# T07_-Schematic_V3.net
KiCad netlist of a schematic drawn in EAGLE
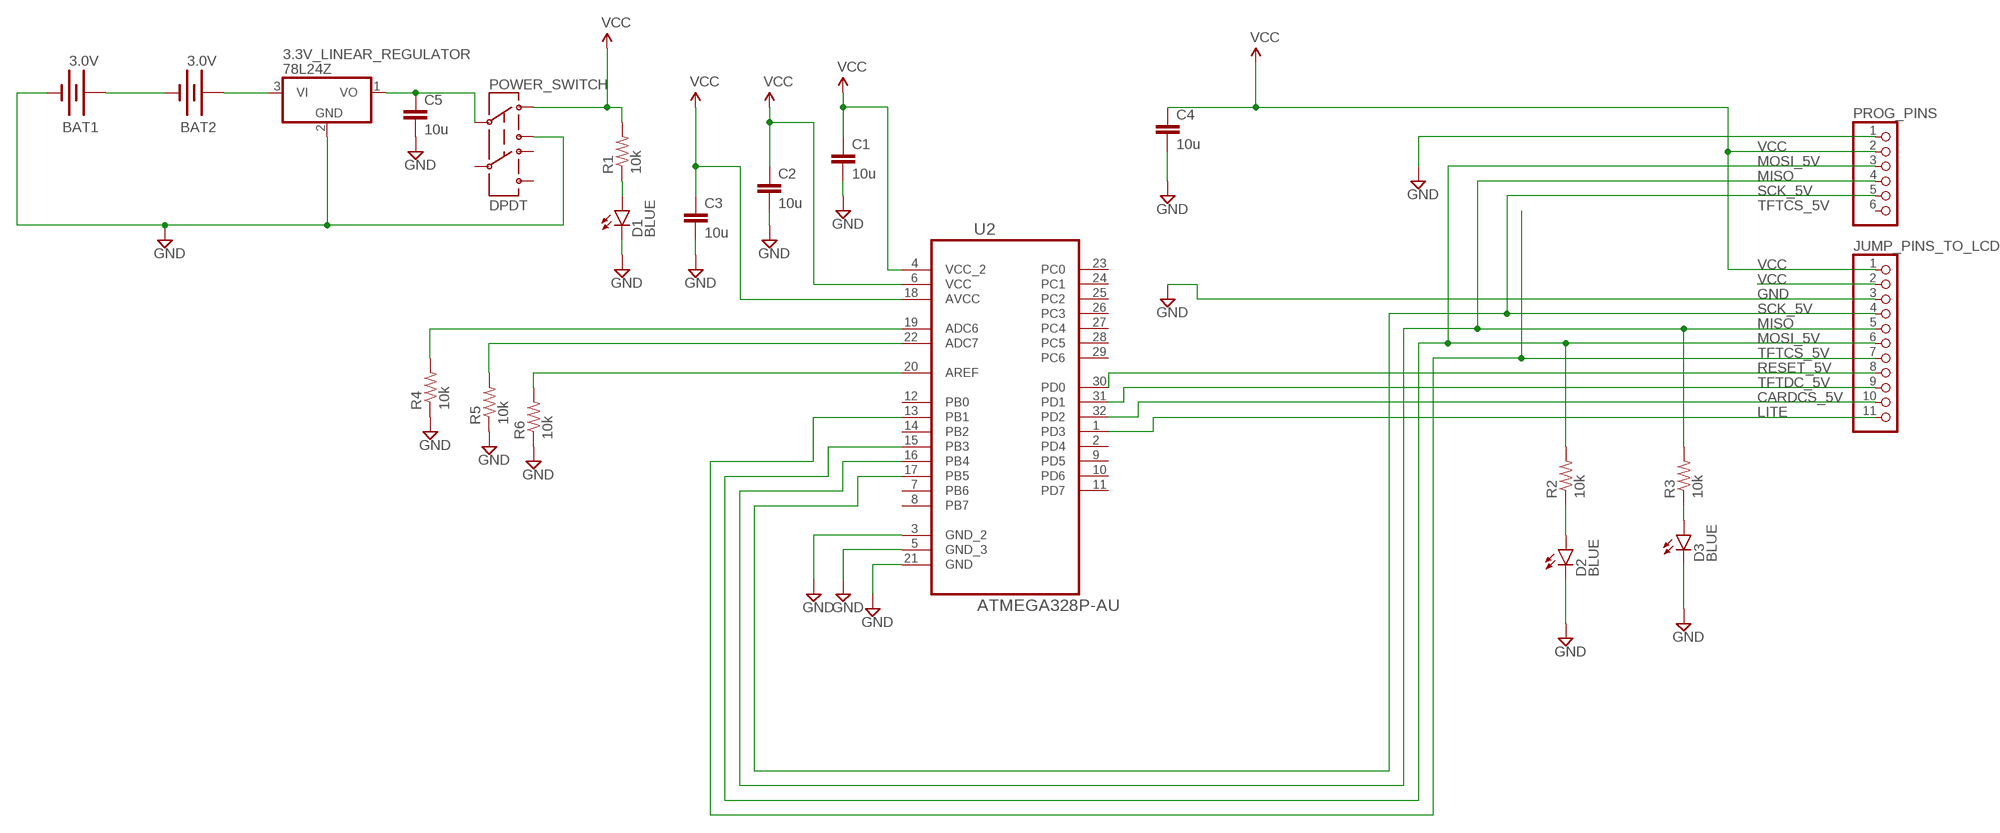
[diagram p0: schematic, sheet 1]

(export (version "E")
  (design (tool "Eeschema 10.0.6"))
  (components
    (comp (ref "3.3V_LINEAR_REGULATOR")
      (value "78L24Z")
      (footprint "eagle-import:TO92")
      (libsource (lib "eagle-import") (part "78ZL24"))
    )
    (comp (ref "BAT1")
      (value "3.0V")
      (footprint "eagle-import:BATTCON_245MM_PTH")
      (libsource (lib "eagle-import") (part "BATTERY245PTH"))
    )
    (comp (ref "BAT2")
      (value "3.0V")
      (footprint "eagle-import:BATTCON_245MM_PTH")
      (libsource (lib "eagle-import") (part "BATTERY245PTH"))
    )
    (comp (ref "C1")
      (value "10u")
      (footprint "eagle-import:1206")
      (libsource (lib "eagle-import") (part "CAP1206"))
    )
    (comp (ref "C2")
      (value "10u")
      (footprint "eagle-import:1206")
      (libsource (lib "eagle-import") (part "CAP1206"))
    )
    (comp (ref "C3")
      (value "10u")
      (footprint "eagle-import:1206")
      (libsource (lib "eagle-import") (part "CAP1206"))
    )
    (comp (ref "C4")
      (value "10u")
      (footprint "eagle-import:1206")
      (libsource (lib "eagle-import") (part "CAP1206"))
    )
    (comp (ref "C5")
      (value "10u")
      (footprint "eagle-import:1206")
      (libsource (lib "eagle-import") (part "CAP1206"))
    )
    (comp (ref "D1")
      (value "BLUE")
      (footprint "eagle-import:LED-1206")
      (libsource (lib "eagle-import") (part "LED-BLUE1206"))
    )
    (comp (ref "D2")
      (value "BLUE")
      (footprint "eagle-import:LED-1206")
      (libsource (lib "eagle-import") (part "LED-BLUE1206"))
    )
    (comp (ref "D3")
      (value "BLUE")
      (footprint "eagle-import:LED-1206")
      (libsource (lib "eagle-import") (part "LED-BLUE1206"))
    )
    (comp (ref "JUMP_PINS_TO_LCD")
      (value "HEADER-1X1176MIL")
      (footprint "eagle-import:1X11_ROUND_76")
      (libsource (lib "eagle-import") (part "HEADER-1X1176MIL"))
    )
    (comp (ref "POWER_SWITCH")
      (value "DPDT")
      (footprint "eagle-import:AYZ0202")
      (libsource (lib "eagle-import") (part "SWITCH-DPDTAYZ0202"))
    )
    (comp (ref "PROG_PINS")
      (value "PINHD-1X6-3.5MM")
      (footprint "eagle-import:1X06-3.5MM")
      (libsource (lib "eagle-import") (part "PINHD-1X6-3.5MM"))
    )
    (comp (ref "R1")
      (value "10k")
      (footprint "eagle-import:1206")
      (libsource (lib "eagle-import") (part "RESISTOR1206"))
    )
    (comp (ref "R2")
      (value "10k")
      (footprint "eagle-import:1206")
      (libsource (lib "eagle-import") (part "RESISTOR1206"))
    )
    (comp (ref "R3")
      (value "10k")
      (footprint "eagle-import:1206")
      (libsource (lib "eagle-import") (part "RESISTOR1206"))
    )
    (comp (ref "R4")
      (value "10k")
      (footprint "eagle-import:1206")
      (libsource (lib "eagle-import") (part "RESISTOR1206"))
    )
    (comp (ref "R5")
      (value "10k")
      (footprint "eagle-import:1206")
      (libsource (lib "eagle-import") (part "RESISTOR1206"))
    )
    (comp (ref "R6")
      (value "10k")
      (footprint "eagle-import:1206")
      (libsource (lib "eagle-import") (part "RESISTOR1206"))
    )
    (comp (ref "U2")
      (value "ATMEGA328P-AU")
      (footprint "eagle-import:QFP80P900X900X120-32N")
      (libsource (lib "eagle-import") (part "ATMEGA328P-AU"))
    )
  )
  (nets
    (net (code "1") (name "/CARDCS_5V") (class "Default")
      (node (ref "JUMP_PINS_TO_LCD") (pin "10") (pinfunction "10_10") (pintype "passive"))
      (node (ref "U2") (pin "32") (pinfunction "PD2_32") (pintype "bidirectional"))
    )
    (net (code "2") (name "/LITE") (class "Default")
      (node (ref "JUMP_PINS_TO_LCD") (pin "11") (pinfunction "11_11") (pintype "passive"))
      (node (ref "U2") (pin "1") (pinfunction "PD3_1") (pintype "bidirectional"))
    )
    (net (code "3") (name "/MISO") (class "Default")
      (node (ref "JUMP_PINS_TO_LCD") (pin "5") (pinfunction "5_5") (pintype "passive"))
      (node (ref "PROG_PINS") (pin "4") (pinfunction "4_4") (pintype "passive"))
      (node (ref "R3") (pin "2") (pinfunction "2_2") (pintype "passive"))
      (node (ref "U2") (pin "16") (pinfunction "PB4_16") (pintype "bidirectional"))
    )
    (net (code "4") (name "/MOSI_5V") (class "Default")
      (node (ref "JUMP_PINS_TO_LCD") (pin "6") (pinfunction "6_6") (pintype "passive"))
      (node (ref "PROG_PINS") (pin "3") (pinfunction "3_3") (pintype "passive"))
      (node (ref "R2") (pin "2") (pinfunction "2_2") (pintype "passive"))
      (node (ref "U2") (pin "15") (pinfunction "PB3_15") (pintype "bidirectional"))
    )
    (net (code "5") (name "/RESET_5V") (class "Default")
      (node (ref "JUMP_PINS_TO_LCD") (pin "8") (pinfunction "8_8") (pintype "passive"))
      (node (ref "U2") (pin "30") (pinfunction "PD0_30") (pintype "bidirectional"))
    )
    (net (code "6") (name "/SCK_5V") (class "Default")
      (node (ref "JUMP_PINS_TO_LCD") (pin "4") (pinfunction "4_4") (pintype "passive"))
      (node (ref "PROG_PINS") (pin "5") (pinfunction "5_5") (pintype "passive"))
      (node (ref "U2") (pin "17") (pinfunction "PB5_17") (pintype "bidirectional"))
    )
    (net (code "7") (name "/TFTCS_5V") (class "Default")
      (node (ref "JUMP_PINS_TO_LCD") (pin "7") (pinfunction "7_7") (pintype "passive"))
      (node (ref "U2") (pin "13") (pinfunction "PB1_13") (pintype "bidirectional"))
    )
    (net (code "8") (name "/TFTDC_5V") (class "Default")
      (node (ref "JUMP_PINS_TO_LCD") (pin "9") (pinfunction "9_9") (pintype "passive"))
      (node (ref "U2") (pin "31") (pinfunction "PD1_31") (pintype "bidirectional"))
    )
    (net (code "9") (name "GND") (class "Default")
      (node (ref "3.3V_LINEAR_REGULATOR") (pin "2") (pinfunction "GND_2") (pintype "passive"))
      (node (ref "BAT1") (pin "2") (pinfunction "-_2") (pintype "power_in"))
      (node (ref "C1") (pin "2") (pinfunction "2_2") (pintype "passive"))
      (node (ref "C2") (pin "2") (pinfunction "2_2") (pintype "passive"))
      (node (ref "C3") (pin "2") (pinfunction "2_2") (pintype "passive"))
      (node (ref "C4") (pin "2") (pinfunction "2_2") (pintype "passive"))
      (node (ref "C5") (pin "2") (pinfunction "2_2") (pintype "passive"))
      (node (ref "D1") (pin "C") (pinfunction "C_C") (pintype "passive"))
      (node (ref "D2") (pin "C") (pinfunction "C_C") (pintype "passive"))
      (node (ref "D3") (pin "C") (pinfunction "C_C") (pintype "passive"))
      (node (ref "JUMP_PINS_TO_LCD") (pin "3") (pinfunction "3_3") (pintype "passive"))
      (node (ref "POWER_SWITCH") (pin "3") (pinfunction "3_3") (pintype "bidirectional"))
      (node (ref "PROG_PINS") (pin "1") (pinfunction "1_1") (pintype "passive"))
      (node (ref "R4") (pin "1") (pinfunction "1_1") (pintype "passive"))
      (node (ref "R5") (pin "1") (pinfunction "1_1") (pintype "passive"))
      (node (ref "R6") (pin "1") (pinfunction "1_1") (pintype "passive"))
      (node (ref "U2") (pin "21") (pinfunction "GND_21") (pintype "passive"))
      (node (ref "U2") (pin "3") (pinfunction "GND_2_3") (pintype "passive"))
      (node (ref "U2") (pin "5") (pinfunction "GND_3_5") (pintype "passive"))
    )
    (net (code "10") (name "Net-(3.3V_LINEAR_REGULATOR-VI)") (class "Default")
      (node (ref "3.3V_LINEAR_REGULATOR") (pin "3") (pinfunction "VI_3") (pintype "input"))
      (node (ref "BAT2") (pin "3") (pinfunction "+_3") (pintype "power_in"))
    )
    (net (code "11") (name "Net-(3.3V_LINEAR_REGULATOR-VO)") (class "Default")
      (node (ref "3.3V_LINEAR_REGULATOR") (pin "1") (pinfunction "VO_1") (pintype "passive"))
      (node (ref "C5") (pin "1") (pinfunction "1_1") (pintype "passive"))
      (node (ref "POWER_SWITCH") (pin "2") (pinfunction "2_2") (pintype "bidirectional"))
    )
    (net (code "12") (name "Net-(BAT1-+)") (class "Default")
      (node (ref "BAT1") (pin "3") (pinfunction "+_3") (pintype "power_in"))
      (node (ref "BAT2") (pin "2") (pinfunction "-_2") (pintype "power_in"))
    )
    (net (code "13") (name "Net-(D1-PadA)") (class "Default")
      (node (ref "D1") (pin "A") (pinfunction "A_A") (pintype "passive"))
      (node (ref "R1") (pin "1") (pinfunction "1_1") (pintype "passive"))
    )
    (net (code "14") (name "Net-(D2-PadA)") (class "Default")
      (node (ref "D2") (pin "A") (pinfunction "A_A") (pintype "passive"))
      (node (ref "R2") (pin "1") (pinfunction "1_1") (pintype "passive"))
    )
    (net (code "15") (name "Net-(D3-PadA)") (class "Default")
      (node (ref "D3") (pin "A") (pinfunction "A_A") (pintype "passive"))
      (node (ref "R3") (pin "1") (pinfunction "1_1") (pintype "passive"))
    )
    (net (code "16") (name "Net-(U2-ADC6)") (class "Default")
      (node (ref "R4") (pin "2") (pinfunction "2_2") (pintype "passive"))
      (node (ref "U2") (pin "19") (pinfunction "ADC6_19") (pintype "input"))
    )
    (net (code "17") (name "Net-(U2-ADC7)") (class "Default")
      (node (ref "R5") (pin "2") (pinfunction "2_2") (pintype "passive"))
      (node (ref "U2") (pin "22") (pinfunction "ADC7_22") (pintype "input"))
    )
    (net (code "18") (name "Net-(U2-AREF)") (class "Default")
      (node (ref "R6") (pin "2") (pinfunction "2_2") (pintype "passive"))
      (node (ref "U2") (pin "20") (pinfunction "AREF_20") (pintype "input"))
    )
    (net (code "19") (name "VCC") (class "Default")
      (node (ref "C1") (pin "1") (pinfunction "1_1") (pintype "passive"))
      (node (ref "C2") (pin "1") (pinfunction "1_1") (pintype "passive"))
      (node (ref "C3") (pin "1") (pinfunction "1_1") (pintype "passive"))
      (node (ref "C4") (pin "1") (pinfunction "1_1") (pintype "passive"))
      (node (ref "JUMP_PINS_TO_LCD") (pin "1") (pinfunction "1_1") (pintype "passive"))
      (node (ref "POWER_SWITCH") (pin "1") (pinfunction "1_1") (pintype "bidirectional"))
      (node (ref "PROG_PINS") (pin "2") (pinfunction "2_2") (pintype "passive"))
      (node (ref "R1") (pin "2") (pinfunction "2_2") (pintype "passive"))
      (node (ref "U2") (pin "18") (pinfunction "AVCC_18") (pintype "power_in"))
      (node (ref "U2") (pin "4") (pinfunction "VCC_2_4") (pintype "power_in"))
      (node (ref "U2") (pin "6") (pinfunction "VCC_6") (pintype "power_in"))
    )
    (net (code "20") (name "unconnected-(JUMP_PINS_TO_LCD-Pad2)") (class "Default")
      (node (ref "JUMP_PINS_TO_LCD") (pin "2") (pinfunction "2_2") (pintype "passive"))
    )
    (net (code "21") (name "unconnected-(POWER_SWITCH-Pad4)") (class "Default")
      (node (ref "POWER_SWITCH") (pin "4") (pinfunction "4_4") (pintype "bidirectional"))
    )
    (net (code "22") (name "unconnected-(POWER_SWITCH-Pad5)") (class "Default")
      (node (ref "POWER_SWITCH") (pin "5") (pinfunction "5_5") (pintype "bidirectional"))
    )
    (net (code "23") (name "unconnected-(POWER_SWITCH-Pad6)") (class "Default")
      (node (ref "POWER_SWITCH") (pin "6") (pinfunction "6_6") (pintype "bidirectional"))
    )
    (net (code "24") (name "unconnected-(PROG_PINS-Pad6)") (class "Default")
      (node (ref "PROG_PINS") (pin "6") (pinfunction "6_6") (pintype "passive"))
    )
    (net (code "25") (name "unconnected-(U2-PB0-Pad12)") (class "Default")
      (node (ref "U2") (pin "12") (pinfunction "PB0_12") (pintype "bidirectional"))
    )
    (net (code "26") (name "unconnected-(U2-PB2-Pad14)") (class "Default")
      (node (ref "U2") (pin "14") (pinfunction "PB2_14") (pintype "bidirectional"))
    )
    (net (code "27") (name "unconnected-(U2-PB6-Pad7)") (class "Default")
      (node (ref "U2") (pin "7") (pinfunction "PB6_7") (pintype "bidirectional"))
    )
    (net (code "28") (name "unconnected-(U2-PB7-Pad8)") (class "Default")
      (node (ref "U2") (pin "8") (pinfunction "PB7_8") (pintype "bidirectional"))
    )
    (net (code "29") (name "unconnected-(U2-PC0-Pad23)") (class "Default")
      (node (ref "U2") (pin "23") (pinfunction "PC0_23") (pintype "bidirectional"))
    )
    (net (code "30") (name "unconnected-(U2-PC1-Pad24)") (class "Default")
      (node (ref "U2") (pin "24") (pinfunction "PC1_24") (pintype "bidirectional"))
    )
    (net (code "31") (name "unconnected-(U2-PC2-Pad25)") (class "Default")
      (node (ref "U2") (pin "25") (pinfunction "PC2_25") (pintype "bidirectional"))
    )
    (net (code "32") (name "unconnected-(U2-PC3-Pad26)") (class "Default")
      (node (ref "U2") (pin "26") (pinfunction "PC3_26") (pintype "bidirectional"))
    )
    (net (code "33") (name "unconnected-(U2-PC4-Pad27)") (class "Default")
      (node (ref "U2") (pin "27") (pinfunction "PC4_27") (pintype "bidirectional"))
    )
    (net (code "34") (name "unconnected-(U2-PC5-Pad28)") (class "Default")
      (node (ref "U2") (pin "28") (pinfunction "PC5_28") (pintype "bidirectional"))
    )
    (net (code "35") (name "unconnected-(U2-PC6-Pad29)") (class "Default")
      (node (ref "U2") (pin "29") (pinfunction "PC6_29") (pintype "bidirectional"))
    )
    (net (code "36") (name "unconnected-(U2-PD4-Pad2)") (class "Default")
      (node (ref "U2") (pin "2") (pinfunction "PD4_2") (pintype "bidirectional"))
    )
    (net (code "37") (name "unconnected-(U2-PD5-Pad9)") (class "Default")
      (node (ref "U2") (pin "9") (pinfunction "PD5_9") (pintype "bidirectional"))
    )
    (net (code "38") (name "unconnected-(U2-PD6-Pad10)") (class "Default")
      (node (ref "U2") (pin "10") (pinfunction "PD6_10") (pintype "bidirectional"))
    )
    (net (code "39") (name "unconnected-(U2-PD7-Pad11)") (class "Default")
      (node (ref "U2") (pin "11") (pinfunction "PD7_11") (pintype "bidirectional"))
    )
  )
)
